# Flashing_LED_23_9.net
KiCad netlist of a schematic drawn in Altium Designer
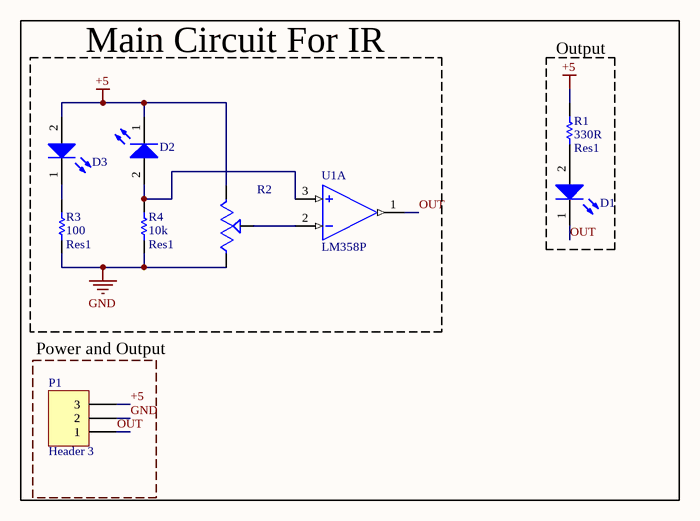
[diagram p0: Flashing_LED_23_9.SchDoc]

(export (version "E")
  (design (tool "Eeschema 10.0.6"))
  (components
    (comp (ref "D1")
      (value "Infrared, 1.5V, 35°")
      (footprint "WL-TIRW_D3.9H5.3")
      (description "WL-TIRW THT Infrared Round Waterclear, D3.9 x H5.3mm, 60mW/sr, Infrared, 1.5V, 35°")
      (fields
        (field (name "MANUFACTURER PART NUMBER") "15400385A3590")
        (field (name "MANUFACTURER") "Wurth Elektronik")
      )
      (libsource (lib "WL-TIRW") (part "15400385A3590"))
    )
    (comp (ref "D2")
      (value "Infrared, 1.5V, 35°")
      (footprint "WL-TIRW_D3.9H5.3")
      (description "WL-TIRW THT Infrared Round Waterclear, D3.9 x H5.3mm, 60mW/sr, Infrared, 1.5V, 35°")
      (fields
        (field (name "MANUFACTURER PART NUMBER") "15400385A3590")
        (field (name "MANUFACTURER") "Wurth Elektronik")
      )
      (libsource (lib "WL-TIRW") (part "15400385A3590"))
    )
    (comp (ref "D3")
      (value "Infrared, 1.5V, 35°")
      (footprint "WL-TIRW_D3.9H5.3")
      (description "WL-TIRW THT Infrared Round Waterclear, D3.9 x H5.3mm, 60mW/sr, Infrared, 1.5V, 35°")
      (fields
        (field (name "MANUFACTURER PART NUMBER") "15400385A3590")
        (field (name "MANUFACTURER") "Wurth Elektronik")
      )
      (libsource (lib "WL-TIRW") (part "15400385A3590"))
    )
    (comp (ref "P1")
      (value "Header 3")
      (footprint "HDR1X3")
      (description "Header, 3-Pin")
      (fields (field (name "PUBLISHER") "Altium Limited"))
      (libsource (lib "Miscellaneous Connectors") (part "Header 3"))
    )
    (comp (ref "R1")
      (value "Res1")
      (footprint "AXIAL-0.3")
      (description "Resistor")
      (fields (field (name "ALTIUM_VALUE") "330R") (field (name "PUBLISHER") "Altium Limited"))
      (libsource (lib "Miscellaneous Devices") (part "Res1"))
    )
    (comp (ref "R2")
      (value "EVN-D8AA03B55")
      (footprint "TRIM_EVN-D8AA03B55")
      (description "500 kOhms 0.1W, 1/10W PC Pins Through Hole Trimmer Potentiometer Carbon 1.0 Turn Top Adjustment")
      (fields (field (name "MF") "Panasonic Electronic"))
      (libsource (lib "EVN-D8AA03B55") (part "EVN-D8AA03B55"))
    )
    (comp (ref "R3")
      (value "Res1")
      (footprint "AXIAL-0.3")
      (description "Resistor")
      (fields (field (name "ALTIUM_VALUE") "100") (field (name "PUBLISHER") "Altium Limited"))
      (libsource (lib "Miscellaneous Devices") (part "Res1"))
    )
    (comp (ref "R4")
      (value "Res1")
      (footprint "AXIAL-0.3")
      (description "Resistor")
      (fields (field (name "ALTIUM_VALUE") "10k") (field (name "PUBLISHER") "Altium Limited"))
      (libsource (lib "Miscellaneous Devices") (part "Res1"))
    )
    (comp (ref "U1")
      (value "LM358P")
      (footprint "DIP794W45P254L959H508Q8")
      (description "Dual, 30-V, 700-kHz operational amplifier")
      (fields (field (name "MF") "Texas Instruments"))
      (libsource (lib "LM358P") (part "LM358P"))
    )
  )
  (nets
    (net (code "1") (name "+5") (class "Default")
      (node (ref "D2") (pin "1") (pinfunction "K_1") (pintype "passive"))
      (node (ref "D3") (pin "2") (pinfunction "A_2") (pintype "passive"))
      (node (ref "P1") (pin "3") (pinfunction "3_3") (pintype "passive"))
      (node (ref "R1") (pin "2") (pinfunction "2_2") (pintype "passive"))
      (node (ref "R2") (pin "3") (pinfunction "3_3") (pintype "passive"))
    )
    (net (code "2") (name "/OUT") (class "Default")
      (node (ref "D1") (pin "1") (pinfunction "K_1") (pintype "passive"))
      (node (ref "P1") (pin "1") (pinfunction "1_1") (pintype "passive"))
      (node (ref "U1") (pin "1") (pinfunction "OUT1_1") (pintype "output"))
    )
    (net (code "3") (name "GND") (class "Default")
      (node (ref "P1") (pin "2") (pinfunction "2_2") (pintype "passive"))
      (node (ref "R2") (pin "1") (pinfunction "1_1") (pintype "passive"))
      (node (ref "R3") (pin "1") (pinfunction "1_1") (pintype "passive"))
      (node (ref "R4") (pin "1") (pinfunction "1_1") (pintype "passive"))
    )
    (net (code "4") (name "Net-(D1-A)") (class "Default")
      (node (ref "D1") (pin "2") (pinfunction "A_2") (pintype "passive"))
      (node (ref "R1") (pin "1") (pinfunction "1_1") (pintype "passive"))
    )
    (net (code "5") (name "Net-(D2-A)") (class "Default")
      (node (ref "D2") (pin "2") (pinfunction "A_2") (pintype "passive"))
      (node (ref "R4") (pin "2") (pinfunction "2_2") (pintype "passive"))
      (node (ref "U1") (pin "3") (pinfunction "+IN1_3") (pintype "input"))
    )
    (net (code "6") (name "Net-(D3-K)") (class "Default")
      (node (ref "D3") (pin "1") (pinfunction "K_1") (pintype "passive"))
      (node (ref "R3") (pin "2") (pinfunction "2_2") (pintype "passive"))
    )
    (net (code "7") (name "Net-(U1A--IN1)") (class "Default")
      (node (ref "R2") (pin "2") (pinfunction "2_2") (pintype "passive"))
      (node (ref "U1") (pin "2") (pinfunction "-IN1_2") (pintype "input"))
    )
  )
)
